# M169_EX.net
KiCad netlist of a schematic drawn in Altium Designer
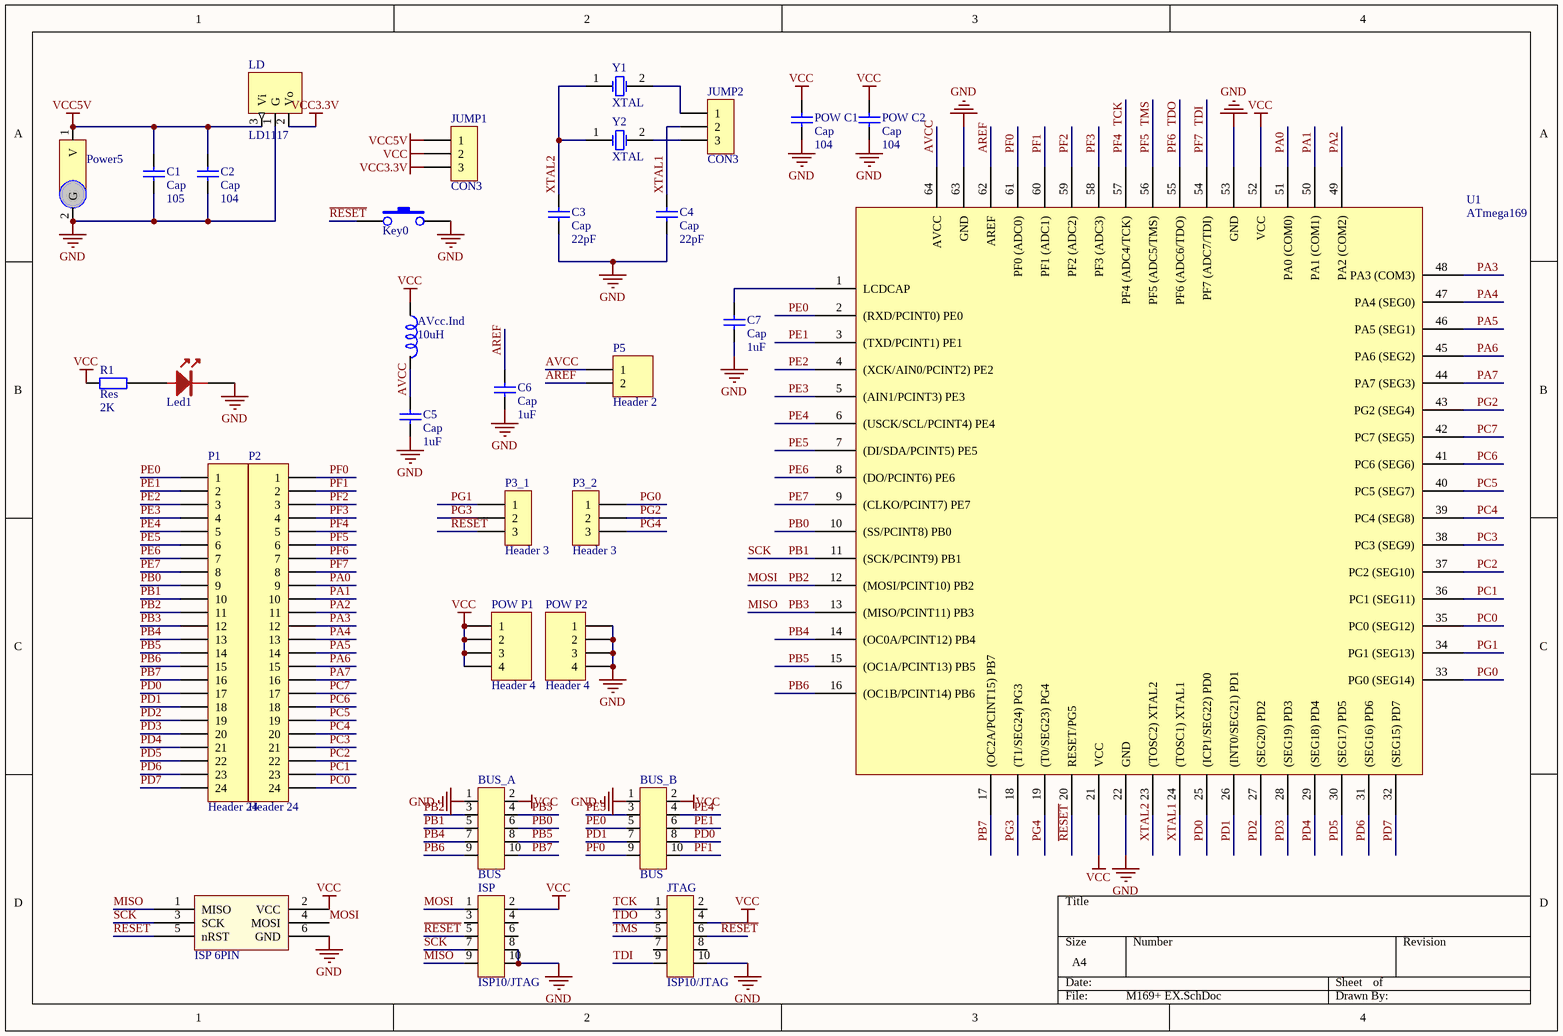
[diagram p0: M169+ EX.SchDoc]

(export (version "E")
  (design (tool "Eeschema 10.0.6"))
  (components
    (comp (ref "AVcc.Ind") (value "10uH") (footprint "RES") (libsource (lib "zz") (part "IND")))
    (comp (ref "BUS_A")
      (value "BUS")
      (footprint "ISP_10")
      (description "ISP_10")
      (libsource (lib "zz") (part "ISP_10"))
    )
    (comp (ref "BUS_B")
      (value "BUS")
      (footprint "ISP_10")
      (description "ISP_10")
      (libsource (lib "zz") (part "ISP_10"))
    )
    (comp (ref "C1")
      (value "Cap")
      (footprint "0805")
      (description "Capacitor")
      (fields (field (name "ALTIUM_VALUE") "105") (field (name "PUBLISHER") "Altium Limited"))
      (libsource (lib "Miscellaneous Devices") (part "Cap"))
    )
    (comp (ref "C2")
      (value "Cap")
      (footprint "0805")
      (description "Capacitor")
      (fields (field (name "ALTIUM_VALUE") "104") (field (name "PUBLISHER") "Altium Limited"))
      (libsource (lib "Miscellaneous Devices") (part "Cap"))
    )
    (comp (ref "C3")
      (value "Cap")
      (footprint "0603")
      (description "Capacitor")
      (fields (field (name "ALTIUM_VALUE") "22pF") (field (name "PUBLISHER") "Altium Limited"))
      (libsource (lib "Miscellaneous Devices") (part "Cap"))
    )
    (comp (ref "C4")
      (value "Cap")
      (footprint "0603")
      (description "Capacitor")
      (fields (field (name "ALTIUM_VALUE") "22pF") (field (name "PUBLISHER") "Altium Limited"))
      (libsource (lib "Miscellaneous Devices") (part "Cap"))
    )
    (comp (ref "C5")
      (value "Cap")
      (footprint "0805")
      (description "Capacitor")
      (fields (field (name "ALTIUM_VALUE") "1uF") (field (name "PUBLISHER") "Altium Limited"))
      (libsource (lib "Miscellaneous Devices") (part "Cap"))
    )
    (comp (ref "C6")
      (value "Cap")
      (footprint "0805")
      (description "Capacitor")
      (fields (field (name "ALTIUM_VALUE") "1uF") (field (name "PUBLISHER") "Altium Limited"))
      (libsource (lib "Miscellaneous Devices") (part "Cap"))
    )
    (comp (ref "C7")
      (value "Cap")
      (footprint "0805")
      (description "Capacitor")
      (fields (field (name "ALTIUM_VALUE") "1uF") (field (name "PUBLISHER") "Altium Limited"))
      (libsource (lib "Miscellaneous Devices") (part "Cap"))
    )
    (comp (ref "ISP")
      (value "ISP10/JTAG")
      (footprint "ISP_10")
      (description "ISP_10")
      (libsource (lib "zz") (part "ISP_10"))
    )
    (comp (ref "ISP 6PIN") (value "ISP 6PIN") (footprint "ISP_6") (libsource (lib "zz") (part "ISP 6PIN")))
    (comp (ref "JTAG")
      (value "ISP10/JTAG")
      (footprint "ISP_10")
      (description "ISP_10")
      (libsource (lib "zz") (part "ISP_10"))
    )
    (comp (ref "JUMP1")
      (value "CON3")
      (footprint "SIP3")
      (description "Connector")
      (libsource (lib "zz") (part "CON3"))
    )
    (comp (ref "JUMP2")
      (value "CON3")
      (footprint "SIP3")
      (description "Connector")
      (libsource (lib "zz") (part "CON3"))
    )
    (comp (ref "Key0") (value "PB2") (footprint "KEY") (libsource (lib "zz") (part "KEY")))
    (comp (ref "LD") (value "LD1117") (footprint "LD1117-3.3") (libsource (lib "zz") (part "LD1117")))
    (comp (ref "Led1") (value "Led1") (footprint "0805_LED") (libsource (lib "zz") (part "LED")))
    (comp (ref "P1")
      (value "Header 24")
      (footprint "SIP24")
      (description "Header, 24-Pin")
      (fields (field (name "PUBLISHER") "Altium Limited"))
      (libsource (lib "") (part "Header 24_1"))
    )
    (comp (ref "P2")
      (value "Header 24")
      (footprint "SIP24")
      (description "Header, 24-Pin")
      (fields (field (name "PUBLISHER") "Altium Limited"))
      (libsource (lib "zz") (part "Header 24"))
    )
    (comp (ref "P3_1")
      (value "Header 3")
      (footprint "SIP3")
      (description "Header, 3-Pin")
      (libsource (lib "zz") (part "Header 3"))
    )
    (comp (ref "P3_2")
      (value "Header 3")
      (footprint "SIP3")
      (description "Header, 3-Pin")
      (libsource (lib "") (part "Header 3_1"))
    )
    (comp (ref "P5")
      (value "Header 2")
      (footprint "SIP2")
      (description "Header, 2-Pin")
      (fields (field (name "PUBLISHER") "Altium Limited"))
      (libsource (lib "zz") (part "Header 2"))
    )
    (comp (ref "POW C1")
      (value "Cap")
      (footprint "0805")
      (description "Capacitor")
      (fields (field (name "ALTIUM_VALUE") "104") (field (name "PUBLISHER") "Altium Limited"))
      (libsource (lib "Miscellaneous Devices") (part "Cap"))
    )
    (comp (ref "POW C2")
      (value "Cap")
      (footprint "0805")
      (description "Capacitor")
      (fields (field (name "ALTIUM_VALUE") "104") (field (name "PUBLISHER") "Altium Limited"))
      (libsource (lib "Miscellaneous Devices") (part "Cap"))
    )
    (comp (ref "POW P1")
      (value "Header 4")
      (footprint "SIP4")
      (description "Header, 4-Pin")
      (fields (field (name "PUBLISHER") "Altium Limited"))
      (libsource (lib "zz") (part "Header 4"))
    )
    (comp (ref "POW P2")
      (value "Header 4")
      (footprint "SIP4")
      (description "Header, 4-Pin")
      (fields (field (name "PUBLISHER") "Altium Limited"))
      (libsource (lib "") (part "Header 4_1"))
    )
    (comp (ref "Power5")
      (value "5V")
      (footprint "PWR_5V")
      (description "Power5")
      (libsource (lib "zz") (part "Power5"))
    )
    (comp (ref "R1")
      (value "Res")
      (footprint "0603")
      (description "Resistor")
      (fields (field (name "ALTIUM_VALUE") "2K") (field (name "PUBLISHER") "Altium Limited"))
      (libsource (lib "Miscellaneous Devices") (part "Res2"))
    )
    (comp (ref "U1") (value "ATmega169") (footprint "TQFP64") (libsource (lib "zz") (part "ATmega169")))
    (comp (ref "Y1")
      (value "XTAL")
      (footprint "CRYSTAL")
      (description "Crystal Oscillator")
      (fields (field (name "PUBLISHER") "Altium Limited"))
      (libsource (lib "zz") (part "XTAL"))
    )
    (comp (ref "Y2")
      (value "XTAL")
      (footprint "CRYSTAL2")
      (description "Crystal Oscillator")
      (fields (field (name "PUBLISHER") "Altium Limited"))
      (libsource (lib "zz") (part "XTAL"))
    )
  )
  (nets
    (net (code "1") (name "/AREF") (class "Default")
      (node (ref "C6") (pin "2") (pinfunction "2_2") (pintype "passive"))
      (node (ref "P5") (pin "2") (pinfunction "2_2") (pintype "passive"))
      (node (ref "U1") (pin "62") (pinfunction "AREF_62") (pintype "passive"))
    )
    (net (code "2") (name "/AVCC") (class "Default")
      (node (ref "AVcc.Ind") (pin "2") (pinfunction "1_2") (pintype "passive"))
      (node (ref "C5") (pin "2") (pinfunction "2_2") (pintype "passive"))
      (node (ref "P5") (pin "1") (pinfunction "1_1") (pintype "passive"))
      (node (ref "U1") (pin "64") (pinfunction "AVCC_64") (pintype "passive"))
    )
    (net (code "3") (name "/MISO") (class "Default")
      (node (ref "BUS_A") (pin "4") (pintype "passive"))
      (node (ref "ISP") (pin "9") (pintype "passive"))
      (node (ref "ISP 6PIN") (pin "1") (pinfunction "MISO_1") (pintype "passive"))
      (node (ref "P1") (pin "12") (pinfunction "12_12") (pintype "passive"))
      (node (ref "U1") (pin "13") (pinfunction "(MISO/PCINT11)_PB3_13") (pintype "passive"))
    )
    (net (code "4") (name "/MOSI") (class "Default")
      (node (ref "BUS_A") (pin "3") (pintype "passive"))
      (node (ref "ISP") (pin "1") (pintype "passive"))
      (node (ref "ISP 6PIN") (pin "4") (pinfunction "MOSI_4") (pintype "passive"))
      (node (ref "P1") (pin "11") (pinfunction "11_11") (pintype "passive"))
      (node (ref "U1") (pin "12") (pinfunction "(MOSI/PCINT10)_PB2_12") (pintype "passive"))
    )
    (net (code "5") (name "/PA0") (class "Default")
      (node (ref "P2") (pin "9") (pinfunction "9_9") (pintype "passive"))
      (node (ref "U1") (pin "51") (pinfunction "PA0_(COM0)_51") (pintype "passive"))
    )
    (net (code "6") (name "/PA1") (class "Default")
      (node (ref "P2") (pin "10") (pinfunction "10_10") (pintype "passive"))
      (node (ref "U1") (pin "50") (pinfunction "PA1_(COM1)_50") (pintype "passive"))
    )
    (net (code "7") (name "/PA2") (class "Default")
      (node (ref "P2") (pin "11") (pinfunction "11_11") (pintype "passive"))
      (node (ref "U1") (pin "49") (pinfunction "PA2_(COM2)_49") (pintype "passive"))
    )
    (net (code "8") (name "/PA3") (class "Default")
      (node (ref "P2") (pin "12") (pinfunction "12_12") (pintype "passive"))
      (node (ref "U1") (pin "48") (pinfunction "PA3_(COM3)_48") (pintype "passive"))
    )
    (net (code "9") (name "/PA4") (class "Default")
      (node (ref "P2") (pin "13") (pinfunction "13_13") (pintype "passive"))
      (node (ref "U1") (pin "47") (pinfunction "PA4_(SEG0)_47") (pintype "passive"))
    )
    (net (code "10") (name "/PA5") (class "Default")
      (node (ref "P2") (pin "14") (pinfunction "14_14") (pintype "passive"))
      (node (ref "U1") (pin "46") (pinfunction "PA5_(SEG1)_46") (pintype "passive"))
    )
    (net (code "11") (name "/PA6") (class "Default")
      (node (ref "P2") (pin "15") (pinfunction "15_15") (pintype "passive"))
      (node (ref "U1") (pin "45") (pinfunction "PA6_(SEG2)_45") (pintype "passive"))
    )
    (net (code "12") (name "/PA7") (class "Default")
      (node (ref "P2") (pin "16") (pinfunction "16_16") (pintype "passive"))
      (node (ref "U1") (pin "44") (pinfunction "PA7_(SEG3)_44") (pintype "passive"))
    )
    (net (code "13") (name "/PB0") (class "Default")
      (node (ref "BUS_A") (pin "6") (pintype "passive"))
      (node (ref "P1") (pin "9") (pinfunction "9_9") (pintype "passive"))
      (node (ref "U1") (pin "10") (pinfunction "(SS/PCINT8)_PB0_10") (pintype "passive"))
    )
    (net (code "14") (name "/PB1") (class "Default")
      (node (ref "BUS_A") (pin "5") (pintype "passive"))
      (node (ref "ISP") (pin "7") (pintype "passive"))
      (node (ref "ISP 6PIN") (pin "3") (pinfunction "SCK_3") (pintype "passive"))
      (node (ref "P1") (pin "10") (pinfunction "10_10") (pintype "passive"))
      (node (ref "U1") (pin "11") (pinfunction "(SCK/PCINT9)_PB1_11") (pintype "passive"))
    )
    (net (code "15") (name "/PB4") (class "Default")
      (node (ref "BUS_A") (pin "7") (pintype "passive"))
      (node (ref "P1") (pin "13") (pinfunction "13_13") (pintype "passive"))
      (node (ref "U1") (pin "14") (pinfunction "(OC0A/PCINT12)_PB4_14") (pintype "passive"))
    )
    (net (code "16") (name "/PB5") (class "Default")
      (node (ref "BUS_A") (pin "8") (pintype "passive"))
      (node (ref "P1") (pin "14") (pinfunction "14_14") (pintype "passive"))
      (node (ref "U1") (pin "15") (pinfunction "(OC1A/PCINT13)_PB5_15") (pintype "passive"))
    )
    (net (code "17") (name "/PB6") (class "Default")
      (node (ref "BUS_A") (pin "9") (pintype "passive"))
      (node (ref "P1") (pin "15") (pinfunction "15_15") (pintype "passive"))
      (node (ref "U1") (pin "16") (pinfunction "(OC1B/PCINT14)_PB6_16") (pintype "passive"))
    )
    (net (code "18") (name "/PB7") (class "Default")
      (node (ref "BUS_A") (pin "10") (pintype "passive"))
      (node (ref "P1") (pin "16") (pinfunction "16_16") (pintype "passive"))
      (node (ref "U1") (pin "17") (pinfunction "(OC2A/PCINT15)_PB7_17") (pintype "passive"))
    )
    (net (code "19") (name "/PC0") (class "Default")
      (node (ref "P2") (pin "24") (pinfunction "24_24") (pintype "passive"))
      (node (ref "U1") (pin "35") (pinfunction "PC0_(SEG12)_35") (pintype "passive"))
    )
    (net (code "20") (name "/PC1") (class "Default")
      (node (ref "P2") (pin "23") (pinfunction "23_23") (pintype "passive"))
      (node (ref "U1") (pin "36") (pinfunction "PC1_(SEG11)_36") (pintype "passive"))
    )
    (net (code "21") (name "/PC2") (class "Default")
      (node (ref "P2") (pin "22") (pinfunction "22_22") (pintype "passive"))
      (node (ref "U1") (pin "37") (pinfunction "PC2_(SEG10)_37") (pintype "passive"))
    )
    (net (code "22") (name "/PC3") (class "Default")
      (node (ref "P2") (pin "21") (pinfunction "21_21") (pintype "passive"))
      (node (ref "U1") (pin "38") (pinfunction "PC3_(SEG9)_38") (pintype "passive"))
    )
    (net (code "23") (name "/PC4") (class "Default")
      (node (ref "P2") (pin "20") (pinfunction "20_20") (pintype "passive"))
      (node (ref "U1") (pin "39") (pinfunction "PC4_(SEG8)_39") (pintype "passive"))
    )
    (net (code "24") (name "/PC5") (class "Default")
      (node (ref "P2") (pin "19") (pinfunction "19_19") (pintype "passive"))
      (node (ref "U1") (pin "40") (pinfunction "PC5_(SEG7)_40") (pintype "passive"))
    )
    (net (code "25") (name "/PC6") (class "Default")
      (node (ref "P2") (pin "18") (pinfunction "18_18") (pintype "passive"))
      (node (ref "U1") (pin "41") (pinfunction "PC6_(SEG6)_41") (pintype "passive"))
    )
    (net (code "26") (name "/PC7") (class "Default")
      (node (ref "P2") (pin "17") (pinfunction "17_17") (pintype "passive"))
      (node (ref "U1") (pin "42") (pinfunction "PC7_(SEG5)_42") (pintype "passive"))
    )
    (net (code "27") (name "/PD0") (class "Default")
      (node (ref "BUS_B") (pin "8") (pintype "passive"))
      (node (ref "P1") (pin "17") (pinfunction "17_17") (pintype "passive"))
      (node (ref "U1") (pin "25") (pinfunction "(ICP1/SEG22)_PD0_25") (pintype "passive"))
    )
    (net (code "28") (name "/PD1") (class "Default")
      (node (ref "BUS_B") (pin "7") (pintype "passive"))
      (node (ref "P1") (pin "18") (pinfunction "18_18") (pintype "passive"))
      (node (ref "U1") (pin "26") (pinfunction "(INT0/SEG21)_PD1_26") (pintype "passive"))
    )
    (net (code "29") (name "/PD2") (class "Default")
      (node (ref "P1") (pin "19") (pinfunction "19_19") (pintype "passive"))
      (node (ref "U1") (pin "27") (pinfunction "(SEG20)_PD2_27") (pintype "passive"))
    )
    (net (code "30") (name "/PD3") (class "Default")
      (node (ref "P1") (pin "20") (pinfunction "20_20") (pintype "passive"))
      (node (ref "U1") (pin "28") (pinfunction "(SEG19)_PD3_28") (pintype "passive"))
    )
    (net (code "31") (name "/PD4") (class "Default")
      (node (ref "P1") (pin "21") (pinfunction "21_21") (pintype "passive"))
      (node (ref "U1") (pin "29") (pinfunction "(SEG18)_PD4_29") (pintype "passive"))
    )
    (net (code "32") (name "/PD5") (class "Default")
      (node (ref "P1") (pin "22") (pinfunction "22_22") (pintype "passive"))
      (node (ref "U1") (pin "30") (pinfunction "(SEG17)_PD5_30") (pintype "passive"))
    )
    (net (code "33") (name "/PD6") (class "Default")
      (node (ref "P1") (pin "23") (pinfunction "23_23") (pintype "passive"))
      (node (ref "U1") (pin "31") (pinfunction "(SEG16)_PD6_31") (pintype "passive"))
    )
    (net (code "34") (name "/PD7") (class "Default")
      (node (ref "P1") (pin "24") (pinfunction "24_24") (pintype "passive"))
      (node (ref "U1") (pin "32") (pinfunction "(SEG15)_PD7_32") (pintype "passive"))
    )
    (net (code "35") (name "/PE0") (class "Default")
      (node (ref "BUS_B") (pin "5") (pintype "passive"))
      (node (ref "P1") (pin "1") (pinfunction "1_1") (pintype "passive"))
      (node (ref "U1") (pin "2") (pinfunction "(RXD/PCINT0)_PE0_2") (pintype "passive"))
    )
    (net (code "36") (name "/PE1") (class "Default")
      (node (ref "BUS_B") (pin "6") (pintype "passive"))
      (node (ref "P1") (pin "2") (pinfunction "2_2") (pintype "passive"))
      (node (ref "U1") (pin "3") (pinfunction "(TXD/PCINT1)_PE1_3") (pintype "passive"))
    )
    (net (code "37") (name "/PE2") (class "Default")
      (node (ref "P1") (pin "3") (pinfunction "3_3") (pintype "passive"))
      (node (ref "U1") (pin "4") (pinfunction "(XCK/AIN0/PCINT2)_PE2_4") (pintype "passive"))
    )
    (net (code "38") (name "/PE3") (class "Default")
      (node (ref "P1") (pin "4") (pinfunction "4_4") (pintype "passive"))
      (node (ref "U1") (pin "5") (pinfunction "(AIN1/PCINT3)_PE3_5") (pintype "passive"))
    )
    (net (code "39") (name "/PE4") (class "Default")
      (node (ref "BUS_B") (pin "4") (pintype "passive"))
      (node (ref "P1") (pin "5") (pinfunction "5_5") (pintype "passive"))
      (node (ref "U1") (pin "6") (pinfunction "(USCK/SCL/PCINT4)_PE4_6") (pintype "passive"))
    )
    (net (code "40") (name "/PE5") (class "Default")
      (node (ref "BUS_B") (pin "3") (pintype "passive"))
      (node (ref "P1") (pin "6") (pinfunction "6_6") (pintype "passive"))
      (node (ref "U1") (pin "7") (pinfunction "(DI/SDA/PCINT5)_PE5_7") (pintype "passive"))
    )
    (net (code "41") (name "/PE6") (class "Default")
      (node (ref "P1") (pin "7") (pinfunction "7_7") (pintype "passive"))
      (node (ref "U1") (pin "8") (pinfunction "(DO/PCINT6)_PE6_8") (pintype "passive"))
    )
    (net (code "42") (name "/PE7") (class "Default")
      (node (ref "P1") (pin "8") (pinfunction "8_8") (pintype "passive"))
      (node (ref "U1") (pin "9") (pinfunction "(CLKO/PCINT7)_PE7_9") (pintype "passive"))
    )
    (net (code "43") (name "/PF0") (class "Default")
      (node (ref "BUS_B") (pin "9") (pintype "passive"))
      (node (ref "P2") (pin "1") (pinfunction "1_1") (pintype "passive"))
      (node (ref "U1") (pin "61") (pinfunction "PF0_(ADC0)_61") (pintype "passive"))
    )
    (net (code "44") (name "/PF1") (class "Default")
      (node (ref "BUS_B") (pin "10") (pintype "passive"))
      (node (ref "P2") (pin "2") (pinfunction "2_2") (pintype "passive"))
      (node (ref "U1") (pin "60") (pinfunction "PF1_(ADC1)_60") (pintype "passive"))
    )
    (net (code "45") (name "/PF2") (class "Default")
      (node (ref "P2") (pin "3") (pinfunction "3_3") (pintype "passive"))
      (node (ref "U1") (pin "59") (pinfunction "PF2_(ADC2)_59") (pintype "passive"))
    )
    (net (code "46") (name "/PF3") (class "Default")
      (node (ref "P2") (pin "4") (pinfunction "4_4") (pintype "passive"))
      (node (ref "U1") (pin "58") (pinfunction "PF3_(ADC3)_58") (pintype "passive"))
    )
    (net (code "47") (name "/PF4") (class "Default")
      (node (ref "JTAG") (pin "1") (pintype "passive"))
      (node (ref "P2") (pin "5") (pinfunction "5_5") (pintype "passive"))
      (node (ref "U1") (pin "57") (pinfunction "PF4_(ADC4/TCK)_57") (pintype "passive"))
    )
    (net (code "48") (name "/PF5") (class "Default")
      (node (ref "JTAG") (pin "5") (pintype "passive"))
      (node (ref "P2") (pin "6") (pinfunction "6_6") (pintype "passive"))
      (node (ref "U1") (pin "56") (pinfunction "PF5_(ADC5/TMS)_56") (pintype "passive"))
    )
    (net (code "49") (name "/PF6") (class "Default")
      (node (ref "JTAG") (pin "3") (pintype "passive"))
      (node (ref "P2") (pin "7") (pinfunction "7_7") (pintype "passive"))
      (node (ref "U1") (pin "55") (pinfunction "PF6_(ADC6/TDO)_55") (pintype "passive"))
    )
    (net (code "50") (name "/PF7") (class "Default")
      (node (ref "JTAG") (pin "9") (pintype "passive"))
      (node (ref "P2") (pin "8") (pinfunction "8_8") (pintype "passive"))
      (node (ref "U1") (pin "54") (pinfunction "PF7_(ADC7/TDI)_54") (pintype "passive"))
    )
    (net (code "51") (name "/PG0") (class "Default")
      (node (ref "P3_2") (pin "1") (pinfunction "1_1") (pintype "passive"))
      (node (ref "U1") (pin "33") (pinfunction "PG0_(SEG14)_33") (pintype "passive"))
    )
    (net (code "52") (name "/PG1") (class "Default")
      (node (ref "P3_1") (pin "1") (pinfunction "1_1") (pintype "passive"))
      (node (ref "U1") (pin "34") (pinfunction "PG1_(SEG13)_34") (pintype "passive"))
    )
    (net (code "53") (name "/PG2") (class "Default")
      (node (ref "P3_2") (pin "2") (pinfunction "2_2") (pintype "passive"))
      (node (ref "U1") (pin "43") (pinfunction "PG2_(SEG4)_43") (pintype "passive"))
    )
    (net (code "54") (name "/PG3") (class "Default")
      (node (ref "P3_1") (pin "2") (pinfunction "2_2") (pintype "passive"))
      (node (ref "U1") (pin "18") (pinfunction "(T1/SEG24)_PG3_18") (pintype "passive"))
    )
    (net (code "55") (name "/PG4") (class "Default")
      (node (ref "P3_2") (pin "3") (pinfunction "3_3") (pintype "passive"))
      (node (ref "U1") (pin "19") (pinfunction "(T0/SEG23)_PG4_19") (pintype "passive"))
    )
    (net (code "56") (name "/XTAL1") (class "Default")
      (node (ref "C4") (pin "2") (pinfunction "2_2") (pintype "passive"))
      (node (ref "JUMP2") (pin "2") (pinfunction "2_2") (pintype "passive"))
      (node (ref "U1") (pin "24") (pinfunction "(TOSC1)_XTAL1_24") (pintype "passive"))
    )
    (net (code "57") (name "/XTAL2") (class "Default")
      (node (ref "C3") (pin "2") (pinfunction "2_2") (pintype "passive"))
      (node (ref "U1") (pin "23") (pinfunction "(TOSC2)_XTAL2_23") (pintype "passive"))
      (node (ref "Y1") (pin "1") (pinfunction "OSC1_1") (pintype "passive"))
      (node (ref "Y2") (pin "1") (pinfunction "OSC1_1") (pintype "passive"))
    )
    (net (code "58") (name "/~{RESET}") (class "Default")
      (node (ref "ISP") (pin "5") (pintype "passive"))
      (node (ref "ISP 6PIN") (pin "5") (pinfunction "nRST_5") (pintype "passive"))
      (node (ref "JTAG") (pin "6") (pintype "passive"))
      (node (ref "Key0") (pin "1") (pinfunction "1_1") (pintype "passive"))
      (node (ref "P3_1") (pin "3") (pinfunction "3_3") (pintype "passive"))
      (node (ref "U1") (pin "20") (pinfunction "RESET/PG5_20") (pintype "passive"))
    )
    (net (code "59") (name "GND") (class "Default")
      (node (ref "BUS_A") (pin "1") (pintype "passive"))
      (node (ref "BUS_B") (pin "1") (pintype "passive"))
      (node (ref "C1") (pin "1") (pinfunction "1_1") (pintype "passive"))
      (node (ref "C2") (pin "1") (pinfunction "1_1") (pintype "passive"))
      (node (ref "C3") (pin "1") (pinfunction "1_1") (pintype "passive"))
      (node (ref "C4") (pin "1") (pinfunction "1_1") (pintype "passive"))
      (node (ref "C5") (pin "1") (pinfunction "1_1") (pintype "passive"))
      (node (ref "C6") (pin "1") (pinfunction "1_1") (pintype "passive"))
      (node (ref "C7") (pin "1") (pinfunction "1_1") (pintype "passive"))
      (node (ref "ISP") (pin "10") (pintype "passive"))
      (node (ref "ISP") (pin "8") (pintype "passive"))
      (node (ref "ISP 6PIN") (pin "6") (pinfunction "GND_6") (pintype "passive"))
      (node (ref "JTAG") (pin "10") (pintype "passive"))
      (node (ref "Key0") (pin "2") (pinfunction "2_2") (pintype "passive"))
      (node (ref "LD") (pin "1") (pinfunction "G_1") (pintype "passive"))
      (node (ref "Led1") (pin "2") (pinfunction "2_2") (pintype "passive"))
      (node (ref "POW C1") (pin "1") (pinfunction "1_1") (pintype "passive"))
      (node (ref "POW C2") (pin "1") (pinfunction "1_1") (pintype "passive"))
      (node (ref "POW P2") (pin "1") (pinfunction "1_1") (pintype "passive"))
      (node (ref "POW P2") (pin "2") (pinfunction "2_2") (pintype "passive"))
      (node (ref "POW P2") (pin "3") (pinfunction "3_3") (pintype "passive"))
      (node (ref "POW P2") (pin "4") (pinfunction "4_4") (pintype "passive"))
      (node (ref "Power5") (pin "2") (pinfunction "G_2") (pintype "passive"))
      (node (ref "U1") (pin "22") (pinfunction "GND_22") (pintype "passive"))
      (node (ref "U1") (pin "53") (pinfunction "GND_53") (pintype "passive"))
      (node (ref "U1") (pin "63") (pinfunction "GND_63") (pintype "passive"))
    )
    (net (code "60") (name "Net-(Led1-Pad1)") (class "Default")
      (node (ref "Led1") (pin "1") (pinfunction "1_1") (pintype "passive"))
      (node (ref "R1") (pin "1") (pinfunction "1_1") (pintype "passive"))
    )
    (net (code "61") (name "Net-(U1-LCDCAP)") (class "Default")
      (node (ref "C7") (pin "2") (pinfunction "2_2") (pintype "passive"))
      (node (ref "U1") (pin "1") (pinfunction "LCDCAP_1") (pintype "passive"))
    )
    (net (code "62") (name "Net-(Y1-OSC2)") (class "Default")
      (node (ref "JUMP2") (pin "1") (pinfunction "1_1") (pintype "passive"))
      (node (ref "Y1") (pin "2") (pinfunction "OSC2_2") (pintype "passive"))
    )
    (net (code "63") (name "Net-(Y2-OSC2)") (class "Default")
      (node (ref "JUMP2") (pin "3") (pinfunction "3_3") (pintype "passive"))
      (node (ref "Y2") (pin "2") (pinfunction "OSC2_2") (pintype "passive"))
    )
    (net (code "64") (name "VCC") (class "Default")
      (node (ref "AVcc.Ind") (pin "1") (pinfunction "0_1") (pintype "passive"))
      (node (ref "BUS_A") (pin "2") (pintype "passive"))
      (node (ref "BUS_B") (pin "2") (pintype "passive"))
      (node (ref "ISP") (pin "2") (pintype "passive"))
      (node (ref "ISP 6PIN") (pin "2") (pinfunction "VCC_2") (pintype "passive"))
      (node (ref "JTAG") (pin "4") (pintype "passive"))
      (node (ref "JUMP1") (pin "2") (pinfunction "2_2") (pintype "passive"))
      (node (ref "POW C1") (pin "2") (pinfunction "2_2") (pintype "passive"))
      (node (ref "POW C2") (pin "2") (pinfunction "2_2") (pintype "passive"))
      (node (ref "POW P1") (pin "1") (pinfunction "1_1") (pintype "passive"))
      (node (ref "POW P1") (pin "2") (pinfunction "2_2") (pintype "passive"))
      (node (ref "POW P1") (pin "3") (pinfunction "3_3") (pintype "passive"))
      (node (ref "POW P1") (pin "4") (pinfunction "4_4") (pintype "passive"))
      (node (ref "R1") (pin "2") (pinfunction "2_2") (pintype "passive"))
      (node (ref "U1") (pin "21") (pinfunction "VCC_21") (pintype "passive"))
      (node (ref "U1") (pin "52") (pinfunction "VCC_52") (pintype "passive"))
    )
    (net (code "65") (name "VCC3.3V") (class "Default")
      (node (ref "JUMP1") (pin "3") (pinfunction "3_3") (pintype "passive"))
      (node (ref "LD") (pin "2") (pinfunction "Vo_2") (pintype "passive"))
    )
    (net (code "66") (name "VCC5V") (class "Default")
      (node (ref "C1") (pin "2") (pinfunction "2_2") (pintype "passive"))
      (node (ref "C2") (pin "2") (pinfunction "2_2") (pintype "passive"))
      (node (ref "JUMP1") (pin "1") (pinfunction "1_1") (pintype "passive"))
      (node (ref "LD") (pin "3") (pinfunction "Vi_3") (pintype "output"))
      (node (ref "Power5") (pin "1") (pinfunction "V_1") (pintype "passive"))
    )
    (net (code "67") (name "unconnected-(ISP-Pad3)") (class "Default")
      (node (ref "ISP") (pin "3") (pintype "passive"))
    )
    (net (code "68") (name "unconnected-(ISP-Pad4)") (class "Default")
      (node (ref "ISP") (pin "4") (pintype "passive"))
    )
    (net (code "69") (name "unconnected-(ISP-Pad6)") (class "Default")
      (node (ref "ISP") (pin "6") (pintype "passive"))
    )
    (net (code "70") (name "unconnected-(JTAG-Pad2)") (class "Default")
      (node (ref "JTAG") (pin "2") (pintype "passive"))
    )
    (net (code "71") (name "unconnected-(JTAG-Pad7)") (class "Default")
      (node (ref "JTAG") (pin "7") (pintype "passive"))
    )
    (net (code "72") (name "unconnected-(JTAG-Pad8)") (class "Default")
      (node (ref "JTAG") (pin "8") (pintype "passive"))
    )
  )
)
